# brama.net
KiCad netlist of a schematic drawn in EAGLE
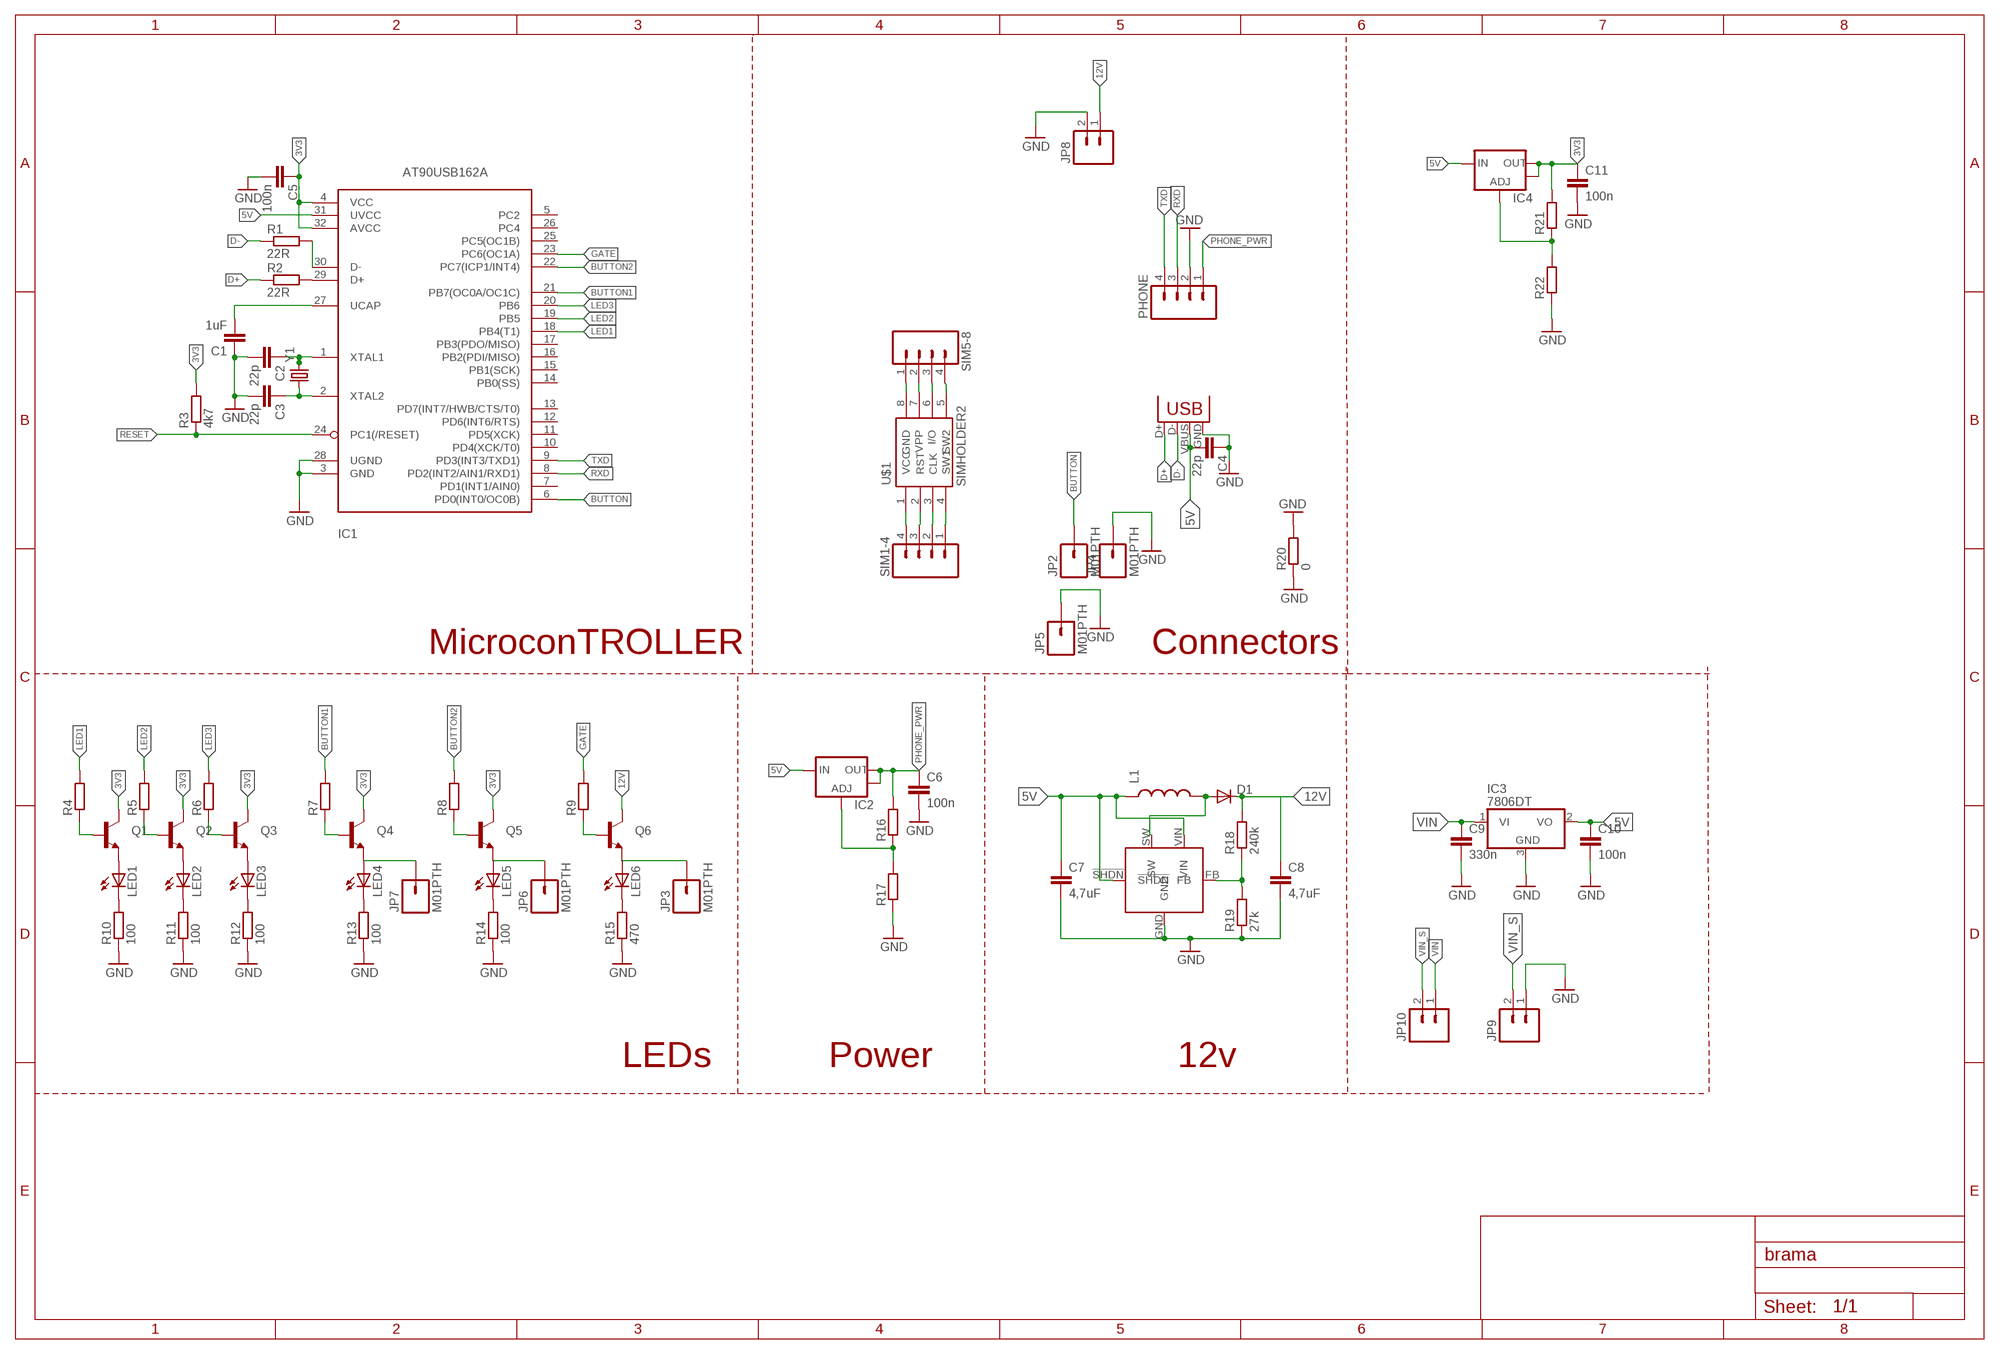
[diagram p0: schematic, sheet 1]

(export (version "E")
  (design (tool "Eeschema 10.0.6"))
  (components
    (comp (ref "C1")
      (value "1uF")
      (footprint "eagle-import:C0805")
      (libsource (lib "eagle-import") (part "C-EUC0805"))
    )
    (comp (ref "C2")
      (value "22p")
      (footprint "eagle-import:C0805")
      (libsource (lib "eagle-import") (part "C-EUC0805"))
    )
    (comp (ref "C3")
      (value "22p")
      (footprint "eagle-import:C0805")
      (libsource (lib "eagle-import") (part "C-EUC0805"))
    )
    (comp (ref "C4")
      (value "22p")
      (footprint "eagle-import:C0805")
      (libsource (lib "eagle-import") (part "C-EUC0805"))
    )
    (comp (ref "C5")
      (value "100n")
      (footprint "eagle-import:C0805")
      (libsource (lib "eagle-import") (part "C-EUC0805"))
    )
    (comp (ref "C6")
      (value "100n")
      (footprint "eagle-import:C0805")
      (libsource (lib "eagle-import") (part "C-EUC0805"))
    )
    (comp (ref "C7")
      (value "4,7uF")
      (footprint "eagle-import:C0805")
      (libsource (lib "eagle-import") (part "C-EUC0805"))
    )
    (comp (ref "C8")
      (value "4,7uF")
      (footprint "eagle-import:C0805")
      (libsource (lib "eagle-import") (part "C-EUC0805"))
    )
    (comp (ref "C9")
      (value "330n")
      (footprint "eagle-import:C0805")
      (libsource (lib "eagle-import") (part "C-EUC0805"))
    )
    (comp (ref "C10")
      (value "100n")
      (footprint "eagle-import:C0805")
      (libsource (lib "eagle-import") (part "C-EUC0805"))
    )
    (comp (ref "C11")
      (value "100n")
      (footprint "eagle-import:C0805")
      (libsource (lib "eagle-import") (part "C-EUC0805"))
    )
    (comp (ref "D1")
      (value "DIODESMB")
      (footprint "eagle-import:SMB-DIODE")
      (libsource (lib "eagle-import") (part "DIODESMB"))
    )
    (comp (ref "IC1")
      (value "AT90USB162A")
      (footprint "eagle-import:TQFP32-08")
      (libsource (lib "eagle-import") (part "AT90USB162A"))
    )
    (comp (ref "IC2")
      (value "V_REG_LM1117SOT223")
      (footprint "eagle-import:SOT223")
      (libsource (lib "eagle-import") (part "V_REG_LM1117SOT223"))
    )
    (comp (ref "IC3")
      (value "7806DT")
      (footprint "eagle-import:TO252")
      (libsource (lib "eagle-import") (part "78DT06"))
    )
    (comp (ref "IC4")
      (value "V_REG_LM1117SOT223")
      (footprint "eagle-import:SOT223")
      (libsource (lib "eagle-import") (part "V_REG_LM1117SOT223"))
    )
    (comp (ref "JP1")
      (value "USBSMD")
      (footprint "eagle-import:USB-MINIB")
      (libsource (lib "eagle-import") (part "USBSMD"))
    )
    (comp (ref "JP2")
      (value "M01PTH")
      (footprint "eagle-import:1X01")
      (libsource (lib "eagle-import") (part "M01PTH"))
    )
    (comp (ref "JP3")
      (value "M01PTH")
      (footprint "eagle-import:1X01")
      (libsource (lib "eagle-import") (part "M01PTH"))
    )
    (comp (ref "JP4")
      (value "M01PTH")
      (footprint "eagle-import:1X01")
      (libsource (lib "eagle-import") (part "M01PTH"))
    )
    (comp (ref "JP5")
      (value "M01PTH")
      (footprint "eagle-import:1X01")
      (libsource (lib "eagle-import") (part "M01PTH"))
    )
    (comp (ref "JP6")
      (value "M01PTH")
      (footprint "eagle-import:1X01")
      (libsource (lib "eagle-import") (part "M01PTH"))
    )
    (comp (ref "JP7")
      (value "M01PTH")
      (footprint "eagle-import:1X01")
      (libsource (lib "eagle-import") (part "M01PTH"))
    )
    (comp (ref "JP8")
      (value "M02PTH3")
      (footprint "eagle-import:1X02_LONGPADS")
      (libsource (lib "eagle-import") (part "M02PTH3"))
    )
    (comp (ref "JP9")
      (value "M02PTH3")
      (footprint "eagle-import:1X02_LONGPADS")
      (libsource (lib "eagle-import") (part "M02PTH3"))
    )
    (comp (ref "JP10")
      (value "M02PTH3")
      (footprint "eagle-import:1X02_LONGPADS")
      (libsource (lib "eagle-import") (part "M02PTH3"))
    )
    (comp (ref "L1")
      (value "INDUCTOR0805")
      (footprint "eagle-import:0805")
      (libsource (lib "eagle-import") (part "INDUCTOR0805"))
    )
    (comp (ref "LED1")
      (value "LEDCHIPLED_0805")
      (footprint "eagle-import:CHIPLED_0805")
      (libsource (lib "eagle-import") (part "LEDCHIPLED_0805"))
    )
    (comp (ref "LED2")
      (value "LEDCHIPLED_0805")
      (footprint "eagle-import:CHIPLED_0805")
      (libsource (lib "eagle-import") (part "LEDCHIPLED_0805"))
    )
    (comp (ref "LED3")
      (value "LEDCHIPLED_0805")
      (footprint "eagle-import:CHIPLED_0805")
      (libsource (lib "eagle-import") (part "LEDCHIPLED_0805"))
    )
    (comp (ref "LED4")
      (value "LEDCHIPLED_0805")
      (footprint "eagle-import:CHIPLED_0805")
      (libsource (lib "eagle-import") (part "LEDCHIPLED_0805"))
    )
    (comp (ref "LED5")
      (value "LEDCHIPLED_0805")
      (footprint "eagle-import:CHIPLED_0805")
      (libsource (lib "eagle-import") (part "LEDCHIPLED_0805"))
    )
    (comp (ref "LED6")
      (value "LEDCHIPLED_0805")
      (footprint "eagle-import:CHIPLED_0805")
      (libsource (lib "eagle-import") (part "LEDCHIPLED_0805"))
    )
    (comp (ref "PHONE")
      (value "M04LONGPADS")
      (footprint "eagle-import:1X04_LONGPADS")
      (libsource (lib "eagle-import") (part "M04LONGPADS"))
    )
    (comp (ref "Q1")
      (value "TRANSISTOR_NPNSOT23")
      (footprint "eagle-import:SOT23")
      (libsource (lib "eagle-import") (part "TRANSISTOR_NPNSOT23"))
    )
    (comp (ref "Q2")
      (value "TRANSISTOR_NPNSOT23")
      (footprint "eagle-import:SOT23")
      (libsource (lib "eagle-import") (part "TRANSISTOR_NPNSOT23"))
    )
    (comp (ref "Q3")
      (value "TRANSISTOR_NPNSOT23")
      (footprint "eagle-import:SOT23")
      (libsource (lib "eagle-import") (part "TRANSISTOR_NPNSOT23"))
    )
    (comp (ref "Q4")
      (value "TRANSISTOR_NPNSOT23")
      (footprint "eagle-import:SOT23")
      (libsource (lib "eagle-import") (part "TRANSISTOR_NPNSOT23"))
    )
    (comp (ref "Q5")
      (value "TRANSISTOR_NPNSOT23")
      (footprint "eagle-import:SOT23")
      (libsource (lib "eagle-import") (part "TRANSISTOR_NPNSOT23"))
    )
    (comp (ref "Q6")
      (value "TRANSISTOR_NPNSOT23")
      (footprint "eagle-import:SOT23")
      (libsource (lib "eagle-import") (part "TRANSISTOR_NPNSOT23"))
    )
    (comp (ref "R1")
      (value "22R")
      (footprint "eagle-import:R0805")
      (libsource (lib "eagle-import") (part "R-EU_R0805"))
    )
    (comp (ref "R2")
      (value "22R")
      (footprint "eagle-import:R0805")
      (libsource (lib "eagle-import") (part "R-EU_R0805"))
    )
    (comp (ref "R3")
      (value "4k7")
      (footprint "eagle-import:R0805")
      (libsource (lib "eagle-import") (part "R-EU_R0805"))
    )
    (comp (ref "R4")
      (value "R-EU_R0805")
      (footprint "eagle-import:R0805")
      (libsource (lib "eagle-import") (part "R-EU_R0805"))
    )
    (comp (ref "R5")
      (value "R-EU_R0805")
      (footprint "eagle-import:R0805")
      (libsource (lib "eagle-import") (part "R-EU_R0805"))
    )
    (comp (ref "R6")
      (value "R-EU_R0805")
      (footprint "eagle-import:R0805")
      (libsource (lib "eagle-import") (part "R-EU_R0805"))
    )
    (comp (ref "R7")
      (value "R-EU_R0805")
      (footprint "eagle-import:R0805")
      (libsource (lib "eagle-import") (part "R-EU_R0805"))
    )
    (comp (ref "R8")
      (value "R-EU_R0805")
      (footprint "eagle-import:R0805")
      (libsource (lib "eagle-import") (part "R-EU_R0805"))
    )
    (comp (ref "R9")
      (value "R-EU_R0805")
      (footprint "eagle-import:R0805")
      (libsource (lib "eagle-import") (part "R-EU_R0805"))
    )
    (comp (ref "R10")
      (value "100")
      (footprint "eagle-import:R0805")
      (libsource (lib "eagle-import") (part "R-EU_R0805"))
    )
    (comp (ref "R11")
      (value "100")
      (footprint "eagle-import:R0805")
      (libsource (lib "eagle-import") (part "R-EU_R0805"))
    )
    (comp (ref "R12")
      (value "100")
      (footprint "eagle-import:R0805")
      (libsource (lib "eagle-import") (part "R-EU_R0805"))
    )
    (comp (ref "R13")
      (value "100")
      (footprint "eagle-import:R0805")
      (libsource (lib "eagle-import") (part "R-EU_R0805"))
    )
    (comp (ref "R14")
      (value "100")
      (footprint "eagle-import:R0805")
      (libsource (lib "eagle-import") (part "R-EU_R0805"))
    )
    (comp (ref "R15")
      (value "470")
      (footprint "eagle-import:R0805")
      (libsource (lib "eagle-import") (part "R-EU_R0805"))
    )
    (comp (ref "R16")
      (value "R-EU_R0805")
      (footprint "eagle-import:R0805")
      (libsource (lib "eagle-import") (part "R-EU_R0805"))
    )
    (comp (ref "R17")
      (value "R-EU_R0805")
      (footprint "eagle-import:R0805")
      (libsource (lib "eagle-import") (part "R-EU_R0805"))
    )
    (comp (ref "R18")
      (value "240k")
      (footprint "eagle-import:R0805")
      (libsource (lib "eagle-import") (part "R-EU_R0805"))
    )
    (comp (ref "R19")
      (value "27k")
      (footprint "eagle-import:R0805")
      (libsource (lib "eagle-import") (part "R-EU_R0805"))
    )
    (comp (ref "R20")
      (value "0")
      (footprint "eagle-import:R0805")
      (libsource (lib "eagle-import") (part "R-EU_R0805"))
    )
    (comp (ref "R21")
      (value "R-EU_R0805")
      (footprint "eagle-import:R0805")
      (libsource (lib "eagle-import") (part "R-EU_R0805"))
    )
    (comp (ref "R22")
      (value "R-EU_R0805")
      (footprint "eagle-import:R0805")
      (libsource (lib "eagle-import") (part "R-EU_R0805"))
    )
    (comp (ref "SIM1-4")
      (value "M04LONGPADS")
      (footprint "eagle-import:1X04_LONGPADS")
      (libsource (lib "eagle-import") (part "M04LONGPADS"))
    )
    (comp (ref "SIM5-8")
      (value "M04LONGPADS")
      (footprint "eagle-import:1X04_LONGPADS")
      (libsource (lib "eagle-import") (part "M04LONGPADS"))
    )
    (comp (ref "U$1")
      (value "SIMHOLDER2")
      (footprint "eagle-import:SIMHOLDER2")
      (libsource (lib "eagle-import") (part "SIMHOLDER2"))
    )
    (comp (ref "U$6")
      (value "LM2704MF-ADJ")
      (footprint "eagle-import:SOT23-5")
      (libsource (lib "eagle-import") (part "LM2704MF-ADJ"))
    )
    (comp (ref "Y1")
      (value "CRYSTALSMD")
      (footprint "eagle-import:HC49UP")
      (libsource (lib "eagle-import") (part "CRYSTALSMD"))
    )
  )
  (nets
    (net (code "1") (name "3V3") (class "Default")
      (node (ref "C11") (pin "1") (pinfunction "1_1") (pintype "passive"))
      (node (ref "C5") (pin "1") (pinfunction "1_1") (pintype "passive"))
      (node (ref "IC1") (pin "32") (pinfunction "AVCC_32") (pintype "bidirectional"))
      (node (ref "IC1") (pin "4") (pinfunction "VCC_4") (pintype "bidirectional"))
      (node (ref "IC4") (pin "2") (pinfunction "OUT_2") (pintype "output"))
      (node (ref "IC4") (pin "4") (pinfunction "OUT_4") (pintype "output"))
      (node (ref "Q1") (pin "3") (pinfunction "C_3") (pintype "passive"))
      (node (ref "Q2") (pin "3") (pinfunction "C_3") (pintype "passive"))
      (node (ref "Q3") (pin "3") (pinfunction "C_3") (pintype "passive"))
      (node (ref "Q4") (pin "3") (pinfunction "C_3") (pintype "passive"))
      (node (ref "Q5") (pin "3") (pinfunction "C_3") (pintype "passive"))
      (node (ref "R21") (pin "2") (pinfunction "2_2") (pintype "passive"))
      (node (ref "R3") (pin "2") (pinfunction "2_2") (pintype "passive"))
    )
    (net (code "2") (name "5V") (class "Default")
      (node (ref "C10") (pin "1") (pinfunction "1_1") (pintype "passive"))
      (node (ref "C4") (pin "2") (pinfunction "2_2") (pintype "passive"))
      (node (ref "C7") (pin "1") (pinfunction "1_1") (pintype "passive"))
      (node (ref "IC1") (pin "31") (pinfunction "UVCC_31") (pintype "bidirectional"))
      (node (ref "IC2") (pin "3") (pinfunction "IN_3") (pintype "input"))
      (node (ref "IC3") (pin "2") (pinfunction "VO_2") (pintype "passive"))
      (node (ref "IC4") (pin "3") (pinfunction "IN_3") (pintype "input"))
      (node (ref "JP1") (pin "VBUS") (pinfunction "VBUS_VBUS") (pintype "bidirectional"))
      (node (ref "L1") (pin "1") (pinfunction "1_1") (pintype "passive"))
      (node (ref "U$6") (pin "!SHDN") (pinfunction "~{SHDN}_!SHDN") (pintype "bidirectional"))
      (node (ref "U$6") (pin "VIN") (pinfunction "VIN_VIN") (pintype "bidirectional"))
    )
    (net (code "3") (name "12V") (class "Default")
      (node (ref "C8") (pin "1") (pinfunction "1_1") (pintype "passive"))
      (node (ref "D1") (pin "C") (pinfunction "C_C") (pintype "passive"))
      (node (ref "JP8") (pin "1") (pinfunction "1_1") (pintype "passive"))
      (node (ref "Q6") (pin "3") (pinfunction "C_3") (pintype "passive"))
      (node (ref "R18") (pin "2") (pinfunction "2_2") (pintype "passive"))
    )
    (net (code "4") (name "BUTTON") (class "Default")
      (node (ref "IC1") (pin "6") (pinfunction "PD0(INT0/OC0B)_6") (pintype "bidirectional"))
      (node (ref "JP2") (pin "1") (pinfunction "1_1") (pintype "passive"))
    )
    (net (code "5") (name "BUTTON1") (class "Default")
      (node (ref "IC1") (pin "21") (pinfunction "PB7(OC0A/OC1C)_21") (pintype "bidirectional"))
      (node (ref "R7") (pin "2") (pinfunction "2_2") (pintype "passive"))
    )
    (net (code "6") (name "BUTTON2") (class "Default")
      (node (ref "IC1") (pin "22") (pinfunction "PC7(ICP1/INT4)_22") (pintype "bidirectional"))
      (node (ref "R8") (pin "2") (pinfunction "2_2") (pintype "passive"))
    )
    (net (code "7") (name "D+") (class "Default")
      (node (ref "JP1") (pin "D+") (pinfunction "D+_D+") (pintype "bidirectional"))
      (node (ref "R2") (pin "1") (pinfunction "1_1") (pintype "passive"))
    )
    (net (code "8") (name "D-") (class "Default")
      (node (ref "JP1") (pin "D-") (pinfunction "D-_D-") (pintype "bidirectional"))
      (node (ref "R1") (pin "1") (pinfunction "1_1") (pintype "passive"))
    )
    (net (code "9") (name "GATE") (class "Default")
      (node (ref "IC1") (pin "23") (pinfunction "PC6(OC1A)_23") (pintype "bidirectional"))
      (node (ref "R9") (pin "2") (pinfunction "2_2") (pintype "passive"))
    )
    (net (code "10") (name "GND") (class "Default")
      (node (ref "C1") (pin "1") (pinfunction "1_1") (pintype "passive"))
      (node (ref "C10") (pin "2") (pinfunction "2_2") (pintype "passive"))
      (node (ref "C11") (pin "2") (pinfunction "2_2") (pintype "passive"))
      (node (ref "C2") (pin "2") (pinfunction "2_2") (pintype "passive"))
      (node (ref "C3") (pin "2") (pinfunction "2_2") (pintype "passive"))
      (node (ref "C4") (pin "1") (pinfunction "1_1") (pintype "passive"))
      (node (ref "C5") (pin "2") (pinfunction "2_2") (pintype "passive"))
      (node (ref "C6") (pin "2") (pinfunction "2_2") (pintype "passive"))
      (node (ref "C7") (pin "2") (pinfunction "2_2") (pintype "passive"))
      (node (ref "C8") (pin "2") (pinfunction "2_2") (pintype "passive"))
      (node (ref "C9") (pin "2") (pinfunction "2_2") (pintype "passive"))
      (node (ref "IC1") (pin "28") (pinfunction "UGND_28") (pintype "bidirectional"))
      (node (ref "IC1") (pin "3") (pinfunction "GND_3") (pintype "bidirectional"))
      (node (ref "IC3") (pin "3") (pinfunction "GND_3") (pintype "passive"))
      (node (ref "JP1") (pin "GND") (pinfunction "GND_GND") (pintype "bidirectional"))
      (node (ref "JP4") (pin "1") (pinfunction "1_1") (pintype "passive"))
      (node (ref "JP5") (pin "1") (pinfunction "1_1") (pintype "passive"))
      (node (ref "JP8") (pin "2") (pinfunction "2_2") (pintype "passive"))
      (node (ref "JP9") (pin "1") (pinfunction "1_1") (pintype "passive"))
      (node (ref "PHONE") (pin "2") (pinfunction "2_2") (pintype "passive"))
      (node (ref "R10") (pin "1") (pinfunction "1_1") (pintype "passive"))
      (node (ref "R11") (pin "1") (pinfunction "1_1") (pintype "passive"))
      (node (ref "R12") (pin "1") (pinfunction "1_1") (pintype "passive"))
      (node (ref "R13") (pin "1") (pinfunction "1_1") (pintype "passive"))
      (node (ref "R14") (pin "1") (pinfunction "1_1") (pintype "passive"))
      (node (ref "R15") (pin "1") (pinfunction "1_1") (pintype "passive"))
      (node (ref "R17") (pin "1") (pinfunction "1_1") (pintype "passive"))
      (node (ref "R19") (pin "1") (pinfunction "1_1") (pintype "passive"))
      (node (ref "R20") (pin "1") (pinfunction "1_1") (pintype "passive"))
      (node (ref "R20") (pin "2") (pinfunction "2_2") (pintype "passive"))
      (node (ref "R22") (pin "1") (pinfunction "1_1") (pintype "passive"))
      (node (ref "U$6") (pin "GND") (pinfunction "GND_GND") (pintype "bidirectional"))
    )
    (net (code "11") (name "LED1") (class "Default")
      (node (ref "IC1") (pin "18") (pinfunction "PB4(T1)_18") (pintype "bidirectional"))
      (node (ref "R4") (pin "2") (pinfunction "2_2") (pintype "passive"))
    )
    (net (code "12") (name "LED2") (class "Default")
      (node (ref "IC1") (pin "19") (pinfunction "PB5_19") (pintype "bidirectional"))
      (node (ref "R5") (pin "2") (pinfunction "2_2") (pintype "passive"))
    )
    (net (code "13") (name "LED3") (class "Default")
      (node (ref "IC1") (pin "20") (pinfunction "PB6_20") (pintype "bidirectional"))
      (node (ref "R6") (pin "2") (pinfunction "2_2") (pintype "passive"))
    )
    (net (code "14") (name "Net-(D1-PadA)") (class "Default")
      (node (ref "D1") (pin "A") (pinfunction "A_A") (pintype "passive"))
      (node (ref "L1") (pin "2") (pinfunction "2_2") (pintype "passive"))
      (node (ref "U$6") (pin "SW") (pinfunction "SW_SW") (pintype "bidirectional"))
    )
    (net (code "15") (name "Net-(IC1-D+)") (class "Default")
      (node (ref "IC1") (pin "29") (pinfunction "D+_29") (pintype "bidirectional"))
      (node (ref "R2") (pin "2") (pinfunction "2_2") (pintype "passive"))
    )
    (net (code "16") (name "Net-(IC1-D-)") (class "Default")
      (node (ref "IC1") (pin "30") (pinfunction "D-_30") (pintype "bidirectional"))
      (node (ref "R1") (pin "2") (pinfunction "2_2") (pintype "passive"))
    )
    (net (code "17") (name "Net-(IC1-UCAP)") (class "Default")
      (node (ref "C1") (pin "2") (pinfunction "2_2") (pintype "passive"))
      (node (ref "IC1") (pin "27") (pinfunction "UCAP_27") (pintype "bidirectional"))
    )
    (net (code "18") (name "Net-(IC1-XTAL1)") (class "Default")
      (node (ref "C2") (pin "1") (pinfunction "1_1") (pintype "passive"))
      (node (ref "IC1") (pin "1") (pinfunction "XTAL1_1") (pintype "bidirectional"))
      (node (ref "Y1") (pin "2") (pinfunction "2_2") (pintype "passive"))
    )
    (net (code "19") (name "Net-(IC1-XTAL2)") (class "Default")
      (node (ref "C3") (pin "1") (pinfunction "1_1") (pintype "passive"))
      (node (ref "IC1") (pin "2") (pinfunction "XTAL2_2") (pintype "bidirectional"))
      (node (ref "Y1") (pin "1") (pinfunction "1_1") (pintype "passive"))
    )
    (net (code "20") (name "Net-(IC2-ADJ)") (class "Default")
      (node (ref "IC2") (pin "1") (pinfunction "ADJ_1") (pintype "input"))
      (node (ref "R16") (pin "1") (pinfunction "1_1") (pintype "passive"))
      (node (ref "R17") (pin "2") (pinfunction "2_2") (pintype "passive"))
    )
    (net (code "21") (name "Net-(IC4-ADJ)") (class "Default")
      (node (ref "IC4") (pin "1") (pinfunction "ADJ_1") (pintype "input"))
      (node (ref "R21") (pin "1") (pinfunction "1_1") (pintype "passive"))
      (node (ref "R22") (pin "2") (pinfunction "2_2") (pintype "passive"))
    )
    (net (code "22") (name "Net-(LED1-PadC)") (class "Default")
      (node (ref "LED1") (pin "C") (pinfunction "C_C") (pintype "passive"))
      (node (ref "R10") (pin "2") (pinfunction "2_2") (pintype "passive"))
    )
    (net (code "23") (name "Net-(LED2-PadC)") (class "Default")
      (node (ref "LED2") (pin "C") (pinfunction "C_C") (pintype "passive"))
      (node (ref "R11") (pin "2") (pinfunction "2_2") (pintype "passive"))
    )
    (net (code "24") (name "Net-(LED3-PadC)") (class "Default")
      (node (ref "LED3") (pin "C") (pinfunction "C_C") (pintype "passive"))
      (node (ref "R12") (pin "2") (pinfunction "2_2") (pintype "passive"))
    )
    (net (code "25") (name "Net-(LED4-PadC)") (class "Default")
      (node (ref "LED4") (pin "C") (pinfunction "C_C") (pintype "passive"))
      (node (ref "R13") (pin "2") (pinfunction "2_2") (pintype "passive"))
    )
    (net (code "26") (name "Net-(LED5-PadC)") (class "Default")
      (node (ref "LED5") (pin "C") (pinfunction "C_C") (pintype "passive"))
      (node (ref "R14") (pin "2") (pinfunction "2_2") (pintype "passive"))
    )
    (net (code "27") (name "Net-(LED6-PadC)") (class "Default")
      (node (ref "LED6") (pin "C") (pinfunction "C_C") (pintype "passive"))
      (node (ref "R15") (pin "2") (pinfunction "2_2") (pintype "passive"))
    )
    (net (code "28") (name "Net-(Q1-B)") (class "Default")
      (node (ref "Q1") (pin "1") (pinfunction "B_1") (pintype "passive"))
      (node (ref "R4") (pin "1") (pinfunction "1_1") (pintype "passive"))
    )
    (net (code "29") (name "Net-(Q1-E)") (class "Default")
      (node (ref "LED1") (pin "A") (pinfunction "A_A") (pintype "passive"))
      (node (ref "Q1") (pin "2") (pinfunction "E_2") (pintype "passive"))
    )
    (net (code "30") (name "Net-(Q2-B)") (class "Default")
      (node (ref "Q2") (pin "1") (pinfunction "B_1") (pintype "passive"))
      (node (ref "R5") (pin "1") (pinfunction "1_1") (pintype "passive"))
    )
    (net (code "31") (name "Net-(Q2-E)") (class "Default")
      (node (ref "LED2") (pin "A") (pinfunction "A_A") (pintype "passive"))
      (node (ref "Q2") (pin "2") (pinfunction "E_2") (pintype "passive"))
    )
    (net (code "32") (name "Net-(Q3-B)") (class "Default")
      (node (ref "Q3") (pin "1") (pinfunction "B_1") (pintype "passive"))
      (node (ref "R6") (pin "1") (pinfunction "1_1") (pintype "passive"))
    )
    (net (code "33") (name "Net-(Q3-E)") (class "Default")
      (node (ref "LED3") (pin "A") (pinfunction "A_A") (pintype "passive"))
      (node (ref "Q3") (pin "2") (pinfunction "E_2") (pintype "passive"))
    )
    (net (code "34") (name "Net-(Q4-B)") (class "Default")
      (node (ref "Q4") (pin "1") (pinfunction "B_1") (pintype "passive"))
      (node (ref "R7") (pin "1") (pinfunction "1_1") (pintype "passive"))
    )
    (net (code "35") (name "Net-(Q4-E)") (class "Default")
      (node (ref "JP7") (pin "1") (pinfunction "1_1") (pintype "passive"))
      (node (ref "LED4") (pin "A") (pinfunction "A_A") (pintype "passive"))
      (node (ref "Q4") (pin "2") (pinfunction "E_2") (pintype "passive"))
    )
    (net (code "36") (name "Net-(Q5-B)") (class "Default")
      (node (ref "Q5") (pin "1") (pinfunction "B_1") (pintype "passive"))
      (node (ref "R8") (pin "1") (pinfunction "1_1") (pintype "passive"))
    )
    (net (code "37") (name "Net-(Q5-E)") (class "Default")
      (node (ref "JP6") (pin "1") (pinfunction "1_1") (pintype "passive"))
      (node (ref "LED5") (pin "A") (pinfunction "A_A") (pintype "passive"))
      (node (ref "Q5") (pin "2") (pinfunction "E_2") (pintype "passive"))
    )
    (net (code "38") (name "Net-(Q6-B)") (class "Default")
      (node (ref "Q6") (pin "1") (pinfunction "B_1") (pintype "passive"))
      (node (ref "R9") (pin "1") (pinfunction "1_1") (pintype "passive"))
    )
    (net (code "39") (name "Net-(Q6-E)") (class "Default")
      (node (ref "JP3") (pin "1") (pinfunction "1_1") (pintype "passive"))
      (node (ref "LED6") (pin "A") (pinfunction "A_A") (pintype "passive"))
      (node (ref "Q6") (pin "2") (pinfunction "E_2") (pintype "passive"))
    )
    (net (code "40") (name "Net-(R18-Pad1)") (class "Default")
      (node (ref "R18") (pin "1") (pinfunction "1_1") (pintype "passive"))
      (node (ref "R19") (pin "2") (pinfunction "2_2") (pintype "passive"))
      (node (ref "U$6") (pin "FB") (pinfunction "FB_FB") (pintype "bidirectional"))
    )
    (net (code "41") (name "Net-(U$1-CLK)") (class "Default")
      (node (ref "SIM1-4") (pin "2") (pinfunction "2_2") (pintype "passive"))
      (node (ref "U$1") (pin "3") (pinfunction "CLK_3") (pintype "bidirectional"))
    )
    (net (code "42") (name "Net-(U$1-GND)") (class "Default")
      (node (ref "SIM5-8") (pin "1") (pinfunction "1_1") (pintype "passive"))
      (node (ref "U$1") (pin "8") (pinfunction "GND_8") (pintype "bidirectional"))
    )
    (net (code "43") (name "Net-(U$1-I{slash}O)") (class "Default")
      (node (ref "SIM5-8") (pin "3") (pinfunction "3_3") (pintype "passive"))
      (node (ref "U$1") (pin "6") (pinfunction "I/O_6") (pintype "bidirectional"))
    )
    (net (code "44") (name "Net-(U$1-RST)") (class "Default")
      (node (ref "SIM1-4") (pin "3") (pinfunction "3_3") (pintype "passive"))
      (node (ref "U$1") (pin "2") (pinfunction "RST_2") (pintype "bidirectional"))
    )
    (net (code "45") (name "Net-(U$1-SW1)") (class "Default")
      (node (ref "SIM1-4") (pin "1") (pinfunction "1_1") (pintype "passive"))
      (node (ref "U$1") (pin "4") (pinfunction "SW1_4") (pintype "bidirectional"))
    )
    (net (code "46") (name "Net-(U$1-SW2)") (class "Default")
      (node (ref "SIM5-8") (pin "4") (pinfunction "4_4") (pintype "passive"))
      (node (ref "U$1") (pin "5") (pinfunction "SW2_5") (pintype "bidirectional"))
    )
    (net (code "47") (name "Net-(U$1-VCC)") (class "Default")
      (node (ref "SIM1-4") (pin "4") (pinfunction "4_4") (pintype "passive"))
      (node (ref "U$1") (pin "1") (pinfunction "VCC_1") (pintype "bidirectional"))
    )
    (net (code "48") (name "Net-(U$1-VPP)") (class "Default")
      (node (ref "SIM5-8") (pin "2") (pinfunction "2_2") (pintype "passive"))
      (node (ref "U$1") (pin "7") (pinfunction "VPP_7") (pintype "bidirectional"))
    )
    (net (code "49") (name "PHONE_PWR") (class "Default")
      (node (ref "C6") (pin "1") (pinfunction "1_1") (pintype "passive"))
      (node (ref "IC2") (pin "2") (pinfunction "OUT_2") (pintype "output"))
      (node (ref "IC2") (pin "4") (pinfunction "OUT_4") (pintype "output"))
      (node (ref "PHONE") (pin "1") (pinfunction "1_1") (pintype "passive"))
      (node (ref "R16") (pin "2") (pinfunction "2_2") (pintype "passive"))
    )
    (net (code "50") (name "RESET") (class "Default")
      (node (ref "IC1") (pin "24") (pinfunction "PC1(/RESET)_24") (pintype "bidirectional"))
      (node (ref "R3") (pin "1") (pinfunction "1_1") (pintype "passive"))
    )
    (net (code "51") (name "RXD") (class "Default")
      (node (ref "IC1") (pin "8") (pinfunction "PD2(INT2/AIN1/RXD1)_8") (pintype "bidirectional"))
      (node (ref "PHONE") (pin "3") (pinfunction "3_3") (pintype "passive"))
    )
    (net (code "52") (name "TXD") (class "Default")
      (node (ref "IC1") (pin "9") (pinfunction "PD3(INT3/TXD1)_9") (pintype "bidirectional"))
      (node (ref "PHONE") (pin "4") (pinfunction "4_4") (pintype "passive"))
    )
    (net (code "53") (name "VIN") (class "Default")
      (node (ref "C9") (pin "1") (pinfunction "1_1") (pintype "passive"))
      (node (ref "IC3") (pin "1") (pinfunction "VI_1") (pintype "input"))
      (node (ref "JP10") (pin "1") (pinfunction "1_1") (pintype "passive"))
    )
    (net (code "54") (name "VIN_S") (class "Default")
      (node (ref "JP10") (pin "2") (pinfunction "2_2") (pintype "passive"))
      (node (ref "JP9") (pin "2") (pinfunction "2_2") (pintype "passive"))
    )
    (net (code "55") (name "unconnected-(IC1-PB0(SS)-Pad14)") (class "Default")
      (node (ref "IC1") (pin "14") (pinfunction "PB0(SS)_14") (pintype "bidirectional"))
    )
    (net (code "56") (name "unconnected-(IC1-PB1(SCK)-Pad15)") (class "Default")
      (node (ref "IC1") (pin "15") (pinfunction "PB1(SCK)_15") (pintype "bidirectional"))
    )
    (net (code "57") (name "unconnected-(IC1-PB2(PDI{slash}MISO)-Pad16)") (class "Default")
      (node (ref "IC1") (pin "16") (pinfunction "PB2(PDI/MISO)_16") (pintype "bidirectional"))
    )
    (net (code "58") (name "unconnected-(IC1-PB3(PDO{slash}MISO)-Pad17)") (class "Default")
      (node (ref "IC1") (pin "17") (pinfunction "PB3(PDO/MISO)_17") (pintype "bidirectional"))
    )
    (net (code "59") (name "unconnected-(IC1-PC2-Pad5)") (class "Default")
      (node (ref "IC1") (pin "5") (pinfunction "PC2_5") (pintype "bidirectional"))
    )
    (net (code "60") (name "unconnected-(IC1-PC4-Pad26)") (class "Default")
      (node (ref "IC1") (pin "26") (pinfunction "PC4_26") (pintype "bidirectional"))
    )
    (net (code "61") (name "unconnected-(IC1-PC5(OC1B)-Pad25)") (class "Default")
      (node (ref "IC1") (pin "25") (pinfunction "PC5(OC1B)_25") (pintype "bidirectional"))
    )
    (net (code "62") (name "unconnected-(IC1-PD1(INT1{slash}AIN0)-Pad7)") (class "Default")
      (node (ref "IC1") (pin "7") (pinfunction "PD1(INT1/AIN0)_7") (pintype "bidirectional"))
    )
    (net (code "63") (name "unconnected-(IC1-PD4(XCK{slash}T0)-Pad10)") (class "Default")
      (node (ref "IC1") (pin "10") (pinfunction "PD4(XCK/T0)_10") (pintype "bidirectional"))
    )
    (net (code "64") (name "unconnected-(IC1-PD5(XCK)-Pad11)") (class "Default")
      (node (ref "IC1") (pin "11") (pinfunction "PD5(XCK)_11") (pintype "bidirectional"))
    )
    (net (code "65") (name "unconnected-(IC1-PD6(INT6{slash}RTS)-Pad12)") (class "Default")
      (node (ref "IC1") (pin "12") (pinfunction "PD6(INT6/RTS)_12") (pintype "bidirectional"))
    )
    (net (code "66") (name "unconnected-(IC1-PD7(INT7{slash}HWB{slash}CTS{slash}T0)-Pad13)") (class "Default")
      (node (ref "IC1") (pin "13") (pinfunction "PD7(INT7/HWB/CTS/T0)_13") (pintype "bidirectional"))
    )
  )
)
